# si5351a.net
KiCad netlist of a schematic drawn in EAGLE
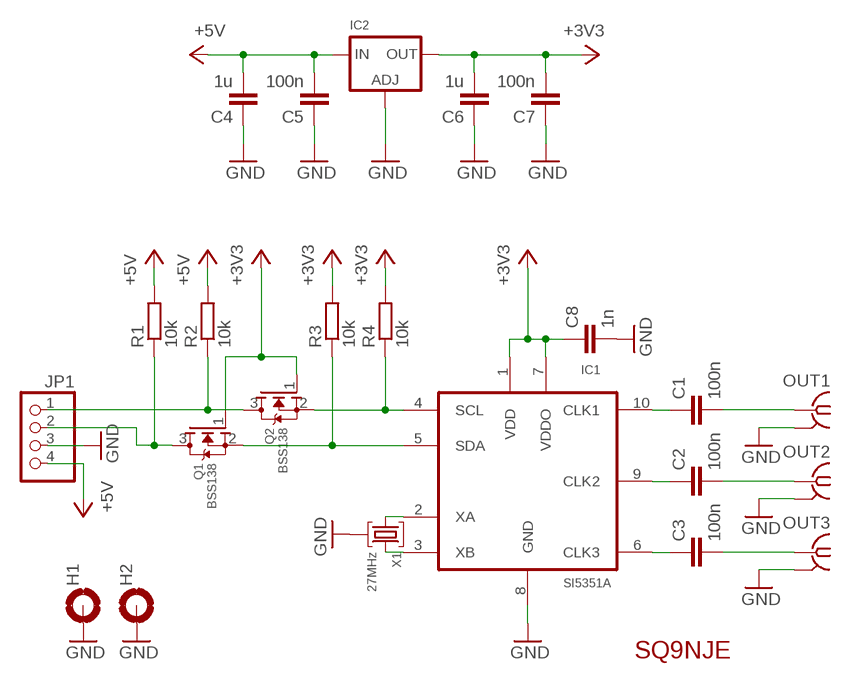
[diagram p0: schematic, sheet 1]

(export (version "E")
  (design (tool "Eeschema 10.0.6"))
  (components
    (comp (ref "C1")
      (value "100n")
      (footprint "eagle-import:0805")
      (libsource (lib "eagle-import") (part "C_0805"))
    )
    (comp (ref "C2")
      (value "100n")
      (footprint "eagle-import:0805")
      (libsource (lib "eagle-import") (part "C_0805"))
    )
    (comp (ref "C3")
      (value "100n")
      (footprint "eagle-import:0805")
      (libsource (lib "eagle-import") (part "C_0805"))
    )
    (comp (ref "C4")
      (value "1u")
      (footprint "eagle-import:0805")
      (libsource (lib "eagle-import") (part "C_0805"))
    )
    (comp (ref "C5")
      (value "100n")
      (footprint "eagle-import:0805")
      (libsource (lib "eagle-import") (part "C_0805"))
    )
    (comp (ref "C6")
      (value "1u")
      (footprint "eagle-import:0805")
      (libsource (lib "eagle-import") (part "C_0805"))
    )
    (comp (ref "C7")
      (value "100n")
      (footprint "eagle-import:0805")
      (libsource (lib "eagle-import") (part "C_0805"))
    )
    (comp (ref "C8")
      (value "1n")
      (footprint "eagle-import:0805")
      (libsource (lib "eagle-import") (part "C_0805"))
    )
    (comp (ref "H1")
      (value "MOUNT-PAD-ROUND3.0")
      (footprint "eagle-import:3,0-PAD")
      (libsource (lib "eagle-import") (part "MOUNT-PAD-ROUND3.0"))
    )
    (comp (ref "H2")
      (value "MOUNT-PAD-ROUND3.0")
      (footprint "eagle-import:3,0-PAD")
      (libsource (lib "eagle-import") (part "MOUNT-PAD-ROUND3.0"))
    )
    (comp (ref "IC1")
      (value "SI5351A")
      (footprint "eagle-import:MSOP10")
      (libsource (lib "eagle-import") (part "SI5351A"))
    )
    (comp (ref "IC2")
      (value "LM1117SOT223-REFLOW")
      (footprint "eagle-import:SOT223-R")
      (libsource (lib "eagle-import") (part "LM1117SOT223-REFLOW"))
    )
    (comp (ref "JP1")
      (value "PINHD-1X04_2.54-90°")
      (footprint "eagle-import:1X04_90")
      (libsource (lib "eagle-import") (part "PINHD-1X04_2.54-90°"))
    )
    (comp (ref "OUT1")
      (value "SMA-142-0711-821/826")
      (footprint "eagle-import:J502-ND-142-0711-821_826")
      (fields (field (name "MF") "JOHNSON COMPONENTS") (field (name "MPN") "142-0711-821"))
      (libsource (lib "eagle-import") (part "SMA-142-0711-821/826"))
    )
    (comp (ref "OUT2")
      (value "SMA-142-0711-821/826")
      (footprint "eagle-import:J502-ND-142-0711-821_826")
      (fields (field (name "MF") "JOHNSON COMPONENTS") (field (name "MPN") "142-0711-821"))
      (libsource (lib "eagle-import") (part "SMA-142-0711-821/826"))
    )
    (comp (ref "OUT3")
      (value "SMA-142-0711-821/826")
      (footprint "eagle-import:J502-ND-142-0711-821_826")
      (fields (field (name "MF") "JOHNSON COMPONENTS") (field (name "MPN") "142-0711-821"))
      (libsource (lib "eagle-import") (part "SMA-142-0711-821/826"))
    )
    (comp (ref "Q1")
      (value "BSS138")
      (footprint "eagle-import:SOT23-R")
      (libsource (lib "eagle-import") (part "MOSFET-NREFLOW"))
    )
    (comp (ref "Q2")
      (value "BSS138")
      (footprint "eagle-import:SOT23-R")
      (libsource (lib "eagle-import") (part "MOSFET-NREFLOW"))
    )
    (comp (ref "R1")
      (value "10k")
      (footprint "eagle-import:0805")
      (libsource (lib "eagle-import") (part "R_0805"))
    )
    (comp (ref "R2")
      (value "10k")
      (footprint "eagle-import:0805")
      (libsource (lib "eagle-import") (part "R_0805"))
    )
    (comp (ref "R3")
      (value "10k")
      (footprint "eagle-import:0805")
      (libsource (lib "eagle-import") (part "R_0805"))
    )
    (comp (ref "R4")
      (value "10k")
      (footprint "eagle-import:0805")
      (libsource (lib "eagle-import") (part "R_0805"))
    )
    (comp (ref "U$1")
      (value "SQ9NJE")
      (footprint "eagle-import:SQ9NJE")
      (libsource (lib "eagle-import") (part "SQ9NJE"))
    )
    (comp (ref "X1")
      (value "27MHz")
      (footprint "eagle-import:TXC")
      (libsource (lib "eagle-import") (part "XTAL_TCX"))
    )
  )
  (nets
    (net (code "1") (name "+3V3") (class "Default")
      (node (ref "C6") (pin "2") (pinfunction "2_2") (pintype "passive"))
      (node (ref "C7") (pin "2") (pinfunction "2_2") (pintype "passive"))
      (node (ref "C8") (pin "1") (pinfunction "1_1") (pintype "passive"))
      (node (ref "IC1") (pin "1") (pinfunction "VDD_1") (pintype "bidirectional"))
      (node (ref "IC1") (pin "7") (pinfunction "VDDO_7") (pintype "bidirectional"))
      (node (ref "IC2") (pin "2") (pinfunction "OUT_2") (pintype "passive"))
      (node (ref "Q1") (pin "1") (pinfunction "G_1") (pintype "bidirectional"))
      (node (ref "Q2") (pin "1") (pinfunction "G_1") (pintype "bidirectional"))
      (node (ref "R3") (pin "2") (pinfunction "2_2") (pintype "passive"))
      (node (ref "R4") (pin "2") (pinfunction "2_2") (pintype "passive"))
    )
    (net (code "2") (name "+5V") (class "Default")
      (node (ref "C4") (pin "2") (pinfunction "2_2") (pintype "passive"))
      (node (ref "C5") (pin "2") (pinfunction "2_2") (pintype "passive"))
      (node (ref "IC2") (pin "3") (pinfunction "IN_3") (pintype "input"))
      (node (ref "JP1") (pin "4") (pinfunction "4_4") (pintype "passive"))
      (node (ref "R1") (pin "2") (pinfunction "2_2") (pintype "passive"))
      (node (ref "R2") (pin "2") (pinfunction "2_2") (pintype "passive"))
    )
    (net (code "3") (name "GND") (class "Default")
      (node (ref "C4") (pin "1") (pinfunction "1_1") (pintype "passive"))
      (node (ref "C5") (pin "1") (pinfunction "1_1") (pintype "passive"))
      (node (ref "C6") (pin "1") (pinfunction "1_1") (pintype "passive"))
      (node (ref "C7") (pin "1") (pinfunction "1_1") (pintype "passive"))
      (node (ref "C8") (pin "2") (pinfunction "2_2") (pintype "passive"))
      (node (ref "H1") (pin "B3,0") (pinfunction "MOUNT_B3,0") (pintype "passive"))
      (node (ref "H2") (pin "B3,0") (pinfunction "MOUNT_B3,0") (pintype "passive"))
      (node (ref "IC1") (pin "8") (pinfunction "GND_8") (pintype "bidirectional"))
      (node (ref "IC2") (pin "1") (pinfunction "ADJ_1") (pintype "input"))
      (node (ref "JP1") (pin "3") (pinfunction "3_3") (pintype "passive"))
      (node (ref "OUT1") (pin "G@1") (pinfunction "2_G@1") (pintype "passive"))
      (node (ref "OUT1") (pin "G@2") (pinfunction "2_G@2") (pintype "passive"))
      (node (ref "OUT1") (pin "G@3") (pinfunction "2_G@3") (pintype "passive"))
      (node (ref "OUT1") (pin "G@4") (pinfunction "2_G@4") (pintype "passive"))
      (node (ref "OUT2") (pin "G@1") (pinfunction "2_G@1") (pintype "passive"))
      (node (ref "OUT2") (pin "G@2") (pinfunction "2_G@2") (pintype "passive"))
      (node (ref "OUT2") (pin "G@3") (pinfunction "2_G@3") (pintype "passive"))
      (node (ref "OUT2") (pin "G@4") (pinfunction "2_G@4") (pintype "passive"))
      (node (ref "OUT3") (pin "G@1") (pinfunction "2_G@1") (pintype "passive"))
      (node (ref "OUT3") (pin "G@2") (pinfunction "2_G@2") (pintype "passive"))
      (node (ref "OUT3") (pin "G@3") (pinfunction "2_G@3") (pintype "passive"))
      (node (ref "OUT3") (pin "G@4") (pinfunction "2_G@4") (pintype "passive"))
      (node (ref "X1") (pin "2") (pinfunction "2_2") (pintype "passive"))
      (node (ref "X1") (pin "4") (pinfunction "2_4") (pintype "passive"))
    )
    (net (code "4") (name "Net-(C1-Pad2)") (class "Default")
      (node (ref "C1") (pin "2") (pinfunction "2_2") (pintype "passive"))
      (node (ref "OUT1") (pin "1") (pinfunction "1_1") (pintype "passive"))
    )
    (net (code "5") (name "Net-(C2-Pad2)") (class "Default")
      (node (ref "C2") (pin "2") (pinfunction "2_2") (pintype "passive"))
      (node (ref "OUT2") (pin "1") (pinfunction "1_1") (pintype "passive"))
    )
    (net (code "6") (name "Net-(C3-Pad2)") (class "Default")
      (node (ref "C3") (pin "2") (pinfunction "2_2") (pintype "passive"))
      (node (ref "OUT3") (pin "1") (pinfunction "1_1") (pintype "passive"))
    )
    (net (code "7") (name "Net-(IC1-CLK1)") (class "Default")
      (node (ref "C1") (pin "1") (pinfunction "1_1") (pintype "passive"))
      (node (ref "IC1") (pin "10") (pinfunction "CLK1_10") (pintype "bidirectional"))
    )
    (net (code "8") (name "Net-(IC1-CLK2)") (class "Default")
      (node (ref "C2") (pin "1") (pinfunction "1_1") (pintype "passive"))
      (node (ref "IC1") (pin "9") (pinfunction "CLK2_9") (pintype "bidirectional"))
    )
    (net (code "9") (name "Net-(IC1-CLK3)") (class "Default")
      (node (ref "C3") (pin "1") (pinfunction "1_1") (pintype "passive"))
      (node (ref "IC1") (pin "6") (pinfunction "CLK3_6") (pintype "bidirectional"))
    )
    (net (code "10") (name "Net-(IC1-SCL)") (class "Default")
      (node (ref "IC1") (pin "4") (pinfunction "SCL_4") (pintype "bidirectional"))
      (node (ref "Q2") (pin "2") (pinfunction "S_2") (pintype "bidirectional"))
      (node (ref "R4") (pin "1") (pinfunction "1_1") (pintype "passive"))
    )
    (net (code "11") (name "Net-(IC1-SDA)") (class "Default")
      (node (ref "IC1") (pin "5") (pinfunction "SDA_5") (pintype "bidirectional"))
      (node (ref "Q1") (pin "2") (pinfunction "S_2") (pintype "bidirectional"))
      (node (ref "R3") (pin "1") (pinfunction "1_1") (pintype "passive"))
    )
    (net (code "12") (name "Net-(IC1-XA)") (class "Default")
      (node (ref "IC1") (pin "2") (pinfunction "XA_2") (pintype "bidirectional"))
      (node (ref "X1") (pin "1") (pinfunction "1_1") (pintype "passive"))
    )
    (net (code "13") (name "Net-(IC1-XB)") (class "Default")
      (node (ref "IC1") (pin "3") (pinfunction "XB_3") (pintype "bidirectional"))
      (node (ref "X1") (pin "3") (pinfunction "3_3") (pintype "passive"))
    )
    (net (code "14") (name "Net-(Q1-D)") (class "Default")
      (node (ref "JP1") (pin "2") (pinfunction "2_2") (pintype "passive"))
      (node (ref "Q1") (pin "3") (pinfunction "D_3") (pintype "bidirectional"))
      (node (ref "R1") (pin "1") (pinfunction "1_1") (pintype "passive"))
    )
    (net (code "15") (name "Net-(Q2-D)") (class "Default")
      (node (ref "JP1") (pin "1") (pinfunction "1_1") (pintype "passive"))
      (node (ref "Q2") (pin "3") (pinfunction "D_3") (pintype "bidirectional"))
      (node (ref "R2") (pin "1") (pinfunction "1_1") (pintype "passive"))
    )
  )
)
